# SensorTestRig_V1.net
KiCad netlist of a schematic drawn in EAGLE
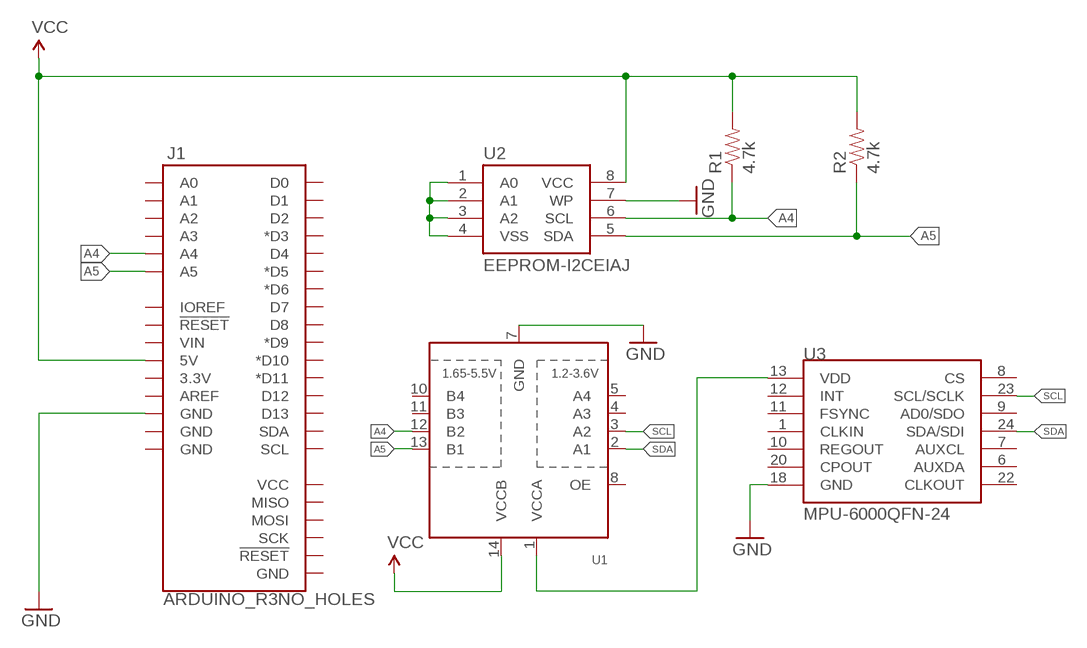
[diagram p0: schematic, sheet 1]

(export (version "E")
  (design (tool "Eeschema 10.0.6"))
  (components
    (comp (ref "J1")
      (value "ARDUINO_R3NO_HOLES")
      (footprint "eagle-import:ARDUINO_R3_NO_HOLES")
      (libsource (lib "eagle-import") (part "ARDUINO_R3NO_HOLES"))
    )
    (comp (ref "R1")
      (value "4.7k")
      (footprint "eagle-import:AXIAL-0.8")
      (libsource (lib "eagle-import") (part "RESISTORPTH-2W"))
    )
    (comp (ref "R2")
      (value "4.7k")
      (footprint "eagle-import:AXIAL-0.8")
      (libsource (lib "eagle-import") (part "RESISTORPTH-2W"))
    )
    (comp (ref "U1")
      (value "TXB0104PWR")
      (footprint "eagle-import:TSSOP14")
      (libsource (lib "eagle-import") (part "TXB0104PWR"))
    )
    (comp (ref "U2")
      (value "EEPROM-I2CEIAJ")
      (footprint "eagle-import:SO08-EIAJ")
      (libsource (lib "eagle-import") (part "EEPROM-I2CEIAJ"))
    )
    (comp (ref "U3")
      (value "MPU-6000QFN-24")
      (footprint "eagle-import:QFN-24-TESTING")
      (libsource (lib "eagle-import") (part "MPU-6000QFN-24"))
    )
  )
  (nets
    (net (code "1") (name "A4") (class "Default")
      (node (ref "J1") (pin "A4") (pinfunction "A4_A4") (pintype "bidirectional"))
      (node (ref "R1") (pin "P$1") (pinfunction "1_P$1") (pintype "passive"))
      (node (ref "U1") (pin "12") (pinfunction "B2_12") (pintype "bidirectional"))
      (node (ref "U2") (pin "6") (pinfunction "SCL_6") (pintype "bidirectional"))
    )
    (net (code "2") (name "A5") (class "Default")
      (node (ref "J1") (pin "A5") (pinfunction "A5_A5") (pintype "bidirectional"))
      (node (ref "R2") (pin "P$1") (pinfunction "1_P$1") (pintype "passive"))
      (node (ref "U1") (pin "13") (pinfunction "B1_13") (pintype "bidirectional"))
      (node (ref "U2") (pin "5") (pinfunction "SDA_5") (pintype "bidirectional"))
    )
    (net (code "3") (name "GND") (class "Default")
      (node (ref "J1") (pin "GND@4") (pinfunction "GND_GND@4") (pintype "bidirectional"))
      (node (ref "U1") (pin "7") (pinfunction "GND_7") (pintype "bidirectional"))
      (node (ref "U2") (pin "7") (pinfunction "WP_7") (pintype "bidirectional"))
      (node (ref "U3") (pin "18") (pinfunction "GND_18") (pintype "bidirectional"))
    )
    (net (code "4") (name "Net-(U1-VCCA)") (class "Default")
      (node (ref "U1") (pin "1") (pinfunction "VCCA_1") (pintype "bidirectional"))
      (node (ref "U3") (pin "13") (pinfunction "VDD_13") (pintype "bidirectional"))
    )
    (net (code "5") (name "Net-(U2-A0)") (class "Default")
      (node (ref "U2") (pin "1") (pinfunction "A0_1") (pintype "bidirectional"))
      (node (ref "U2") (pin "2") (pinfunction "A1_2") (pintype "bidirectional"))
      (node (ref "U2") (pin "3") (pinfunction "A2_3") (pintype "bidirectional"))
      (node (ref "U2") (pin "4") (pinfunction "VSS_4") (pintype "power_in"))
    )
    (net (code "6") (name "SCL") (class "Default")
      (node (ref "U1") (pin "3") (pinfunction "A2_3") (pintype "bidirectional"))
      (node (ref "U3") (pin "23") (pinfunction "SCL/SCLK_23") (pintype "bidirectional"))
    )
    (net (code "7") (name "SDA") (class "Default")
      (node (ref "U1") (pin "2") (pinfunction "A1_2") (pintype "bidirectional"))
      (node (ref "U3") (pin "24") (pinfunction "SDA/SDI_24") (pintype "bidirectional"))
    )
    (net (code "8") (name "VCC") (class "Default")
      (node (ref "J1") (pin "5V") (pinfunction "5V_5V") (pintype "bidirectional"))
      (node (ref "R1") (pin "P$2") (pinfunction "2_P$2") (pintype "passive"))
      (node (ref "R2") (pin "P$2") (pinfunction "2_P$2") (pintype "passive"))
      (node (ref "U1") (pin "14") (pinfunction "VCCB_14") (pintype "bidirectional"))
      (node (ref "U2") (pin "8") (pinfunction "VCC_8") (pintype "power_in"))
    )
    (net (code "9") (name "unconnected-(J1-*D3-PadD3)") (class "Default")
      (node (ref "J1") (pin "D3") (pinfunction "*D3_D3") (pintype "bidirectional"))
    )
    (net (code "10") (name "unconnected-(J1-*D5-PadD5)") (class "Default")
      (node (ref "J1") (pin "D5") (pinfunction "*D5_D5") (pintype "bidirectional"))
    )
    (net (code "11") (name "unconnected-(J1-*D6-PadD6)") (class "Default")
      (node (ref "J1") (pin "D6") (pinfunction "*D6_D6") (pintype "bidirectional"))
    )
    (net (code "12") (name "unconnected-(J1-*D9-PadD9)") (class "Default")
      (node (ref "J1") (pin "D9") (pinfunction "*D9_D9") (pintype "bidirectional"))
    )
    (net (code "13") (name "unconnected-(J1-*D10-PadD10)") (class "Default")
      (node (ref "J1") (pin "D10") (pinfunction "*D10_D10") (pintype "bidirectional"))
    )
    (net (code "14") (name "unconnected-(J1-*D11-PadD11)") (class "Default")
      (node (ref "J1") (pin "D11") (pinfunction "*D11_D11") (pintype "bidirectional"))
    )
    (net (code "15") (name "unconnected-(J1-GND-PadGND@1)") (class "Default")
      (node (ref "J1") (pin "GND@1") (pinfunction "GND_GND@1") (pintype "bidirectional"))
    )
    (net (code "16") (name "unconnected-(J1-GND-PadGND@2)") (class "Default")
      (node (ref "J1") (pin "GND@2") (pinfunction "GND_GND@2") (pintype "bidirectional"))
    )
    (net (code "17") (name "unconnected-(J1-GND-PadGND@3)") (class "Default")
      (node (ref "J1") (pin "GND@3") (pinfunction "GND_GND@3") (pintype "bidirectional"))
    )
    (net (code "18") (name "unconnected-(J1-Pad3.3V)") (class "Default")
      (node (ref "J1") (pin "3.3V") (pinfunction "3.3V_3.3V") (pintype "bidirectional"))
    )
    (net (code "19") (name "unconnected-(J1-PadA0)") (class "Default")
      (node (ref "J1") (pin "A0") (pinfunction "A0_A0") (pintype "bidirectional"))
    )
    (net (code "20") (name "unconnected-(J1-PadA1)") (class "Default")
      (node (ref "J1") (pin "A1") (pinfunction "A1_A1") (pintype "bidirectional"))
    )
    (net (code "21") (name "unconnected-(J1-PadA2)") (class "Default")
      (node (ref "J1") (pin "A2") (pinfunction "A2_A2") (pintype "bidirectional"))
    )
    (net (code "22") (name "unconnected-(J1-PadA3)") (class "Default")
      (node (ref "J1") (pin "A3") (pinfunction "A3_A3") (pintype "bidirectional"))
    )
    (net (code "23") (name "unconnected-(J1-PadAREF)") (class "Default")
      (node (ref "J1") (pin "AREF") (pinfunction "AREF_AREF") (pintype "bidirectional"))
    )
    (net (code "24") (name "unconnected-(J1-PadD0)") (class "Default")
      (node (ref "J1") (pin "D0") (pinfunction "D0_D0") (pintype "bidirectional"))
    )
    (net (code "25") (name "unconnected-(J1-PadD1)") (class "Default")
      (node (ref "J1") (pin "D1") (pinfunction "D1_D1") (pintype "bidirectional"))
    )
    (net (code "26") (name "unconnected-(J1-PadD2)") (class "Default")
      (node (ref "J1") (pin "D2") (pinfunction "D2_D2") (pintype "bidirectional"))
    )
    (net (code "27") (name "unconnected-(J1-PadD4)") (class "Default")
      (node (ref "J1") (pin "D4") (pinfunction "D4_D4") (pintype "bidirectional"))
    )
    (net (code "28") (name "unconnected-(J1-PadD7)") (class "Default")
      (node (ref "J1") (pin "D7") (pinfunction "D7_D7") (pintype "bidirectional"))
    )
    (net (code "29") (name "unconnected-(J1-PadD8)") (class "Default")
      (node (ref "J1") (pin "D8") (pinfunction "D8_D8") (pintype "bidirectional"))
    )
    (net (code "30") (name "unconnected-(J1-PadD12)") (class "Default")
      (node (ref "J1") (pin "D12") (pinfunction "D12_D12") (pintype "bidirectional"))
    )
    (net (code "31") (name "unconnected-(J1-PadD13)") (class "Default")
      (node (ref "J1") (pin "D13") (pinfunction "D13_D13") (pintype "bidirectional"))
    )
    (net (code "32") (name "unconnected-(J1-PadIOREF)") (class "Default")
      (node (ref "J1") (pin "IOREF") (pinfunction "IOREF_IOREF") (pintype "bidirectional"))
    )
    (net (code "33") (name "unconnected-(J1-PadMISO)") (class "Default")
      (node (ref "J1") (pin "MISO") (pinfunction "MISO_MISO") (pintype "bidirectional"))
    )
    (net (code "34") (name "unconnected-(J1-PadMOSI)") (class "Default")
      (node (ref "J1") (pin "MOSI") (pinfunction "MOSI_MOSI") (pintype "bidirectional"))
    )
    (net (code "35") (name "unconnected-(J1-PadSCK)") (class "Default")
      (node (ref "J1") (pin "SCK") (pinfunction "SCK_SCK") (pintype "bidirectional"))
    )
    (net (code "36") (name "unconnected-(J1-PadSCL)") (class "Default")
      (node (ref "J1") (pin "SCL") (pinfunction "SCL_SCL") (pintype "bidirectional"))
    )
    (net (code "37") (name "unconnected-(J1-PadSDA)") (class "Default")
      (node (ref "J1") (pin "SDA") (pinfunction "SDA_SDA") (pintype "bidirectional"))
    )
    (net (code "38") (name "unconnected-(J1-PadVCC)") (class "Default")
      (node (ref "J1") (pin "VCC") (pinfunction "VCC_VCC") (pintype "bidirectional"))
    )
    (net (code "39") (name "unconnected-(J1-PadVIN)") (class "Default")
      (node (ref "J1") (pin "VIN") (pinfunction "VIN_VIN") (pintype "bidirectional"))
    )
    (net (code "40") (name "unconnected-(J1-~{RESET}-PadRESET@1)") (class "Default")
      (node (ref "J1") (pin "RESET@1") (pinfunction "~{RESET}_RESET@1") (pintype "bidirectional"))
    )
    (net (code "41") (name "unconnected-(J1-~{RESET}-PadRESET@2)") (class "Default")
      (node (ref "J1") (pin "RESET@2") (pinfunction "~{RESET}_RESET@2") (pintype "bidirectional"))
    )
    (net (code "42") (name "unconnected-(U1-A3-Pad4)") (class "Default")
      (node (ref "U1") (pin "4") (pinfunction "A3_4") (pintype "bidirectional"))
    )
    (net (code "43") (name "unconnected-(U1-A4-Pad5)") (class "Default")
      (node (ref "U1") (pin "5") (pinfunction "A4_5") (pintype "bidirectional"))
    )
    (net (code "44") (name "unconnected-(U1-B3-Pad11)") (class "Default")
      (node (ref "U1") (pin "11") (pinfunction "B3_11") (pintype "bidirectional"))
    )
    (net (code "45") (name "unconnected-(U1-B4-Pad10)") (class "Default")
      (node (ref "U1") (pin "10") (pinfunction "B4_10") (pintype "bidirectional"))
    )
    (net (code "46") (name "unconnected-(U1-OE-Pad8)") (class "Default")
      (node (ref "U1") (pin "8") (pinfunction "OE_8") (pintype "bidirectional"))
    )
    (net (code "47") (name "unconnected-(U3-AD0{slash}SDO-Pad9)") (class "Default")
      (node (ref "U3") (pin "9") (pinfunction "AD0/SDO_9") (pintype "bidirectional"))
    )
    (net (code "48") (name "unconnected-(U3-AUXCL-Pad7)") (class "Default")
      (node (ref "U3") (pin "7") (pinfunction "AUXCL_7") (pintype "bidirectional"))
    )
    (net (code "49") (name "unconnected-(U3-AUXDA-Pad6)") (class "Default")
      (node (ref "U3") (pin "6") (pinfunction "AUXDA_6") (pintype "bidirectional"))
    )
    (net (code "50") (name "unconnected-(U3-CLKIN-Pad1)") (class "Default")
      (node (ref "U3") (pin "1") (pinfunction "CLKIN_1") (pintype "bidirectional"))
    )
    (net (code "51") (name "unconnected-(U3-CLKOUT-Pad22)") (class "Default")
      (node (ref "U3") (pin "22") (pinfunction "CLKOUT_22") (pintype "bidirectional"))
    )
    (net (code "52") (name "unconnected-(U3-CPOUT-Pad20)") (class "Default")
      (node (ref "U3") (pin "20") (pinfunction "CPOUT_20") (pintype "bidirectional"))
    )
    (net (code "53") (name "unconnected-(U3-CS-Pad8)") (class "Default")
      (node (ref "U3") (pin "8") (pinfunction "CS_8") (pintype "bidirectional"))
    )
    (net (code "54") (name "unconnected-(U3-FSYNC-Pad11)") (class "Default")
      (node (ref "U3") (pin "11") (pinfunction "FSYNC_11") (pintype "bidirectional"))
    )
    (net (code "55") (name "unconnected-(U3-INT-Pad12)") (class "Default")
      (node (ref "U3") (pin "12") (pinfunction "INT_12") (pintype "bidirectional"))
    )
    (net (code "56") (name "unconnected-(U3-REGOUT-Pad10)") (class "Default")
      (node (ref "U3") (pin "10") (pinfunction "REGOUT_10") (pintype "bidirectional"))
    )
  )
)
